# Zigzag_5p_ATtiny_connector.net
KiCad netlist of a schematic drawn in EAGLE
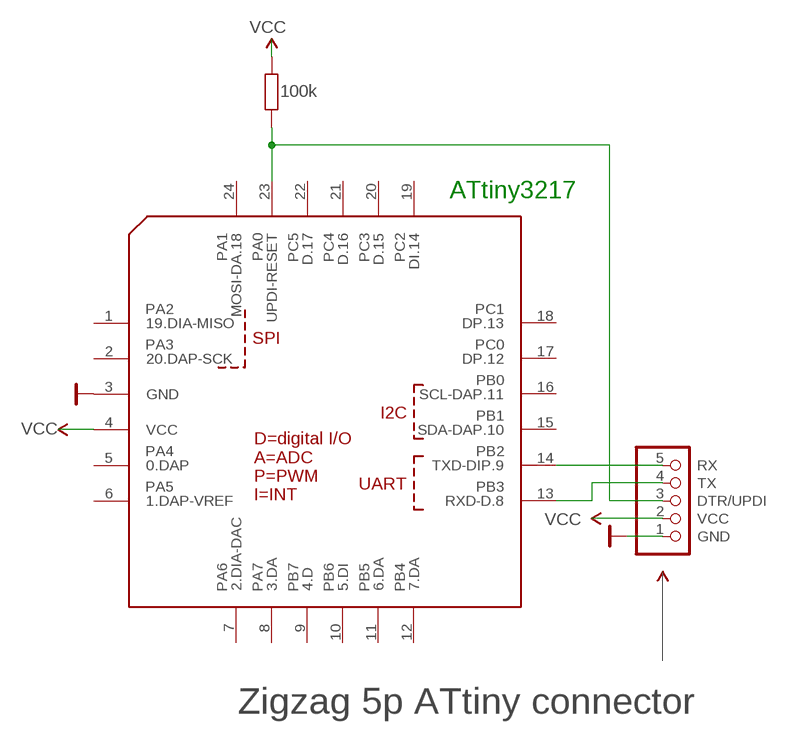
[diagram p0: schematic, sheet 1]

(export (version "E")
  (design (tool "Eeschema 10.0.6"))
  (components
    (comp (ref "J1")
      (value "5 pin 0.05\" ZIGZAG connector")
      (footprint "eagle-import:ZIGZAG-FTDI-UPDI-5P")
      (libsource (lib "eagle-import") (part "ZIGZAG-FTDI-UPDI-5P"))
    )
    (comp (ref "R1")
      (value "100k")
      (footprint "eagle-import:0603")
      (libsource (lib "eagle-import") (part "SMD-R0603"))
    )
    (comp (ref "U2")
      (value "ATtiny3217")
      (footprint "eagle-import:QFN-24")
      (libsource (lib "eagle-import") (part "ATTINY3217-"))
    )
  )
  (nets
    (net (code "1") (name "/VCC") (class "Default")
      (node (ref "J1") (pin "2") (pinfunction "VCC_2") (pintype "passive"))
      (node (ref "R1") (pin "2") (pinfunction "2_2") (pintype "passive"))
      (node (ref "U2") (pin "4") (pinfunction "VCC_4") (pintype "bidirectional"))
    )
    (net (code "2") (name "GND") (class "Default")
      (node (ref "J1") (pin "1") (pinfunction "GND_1") (pintype "passive"))
      (node (ref "U2") (pin "3") (pinfunction "GND_3") (pintype "bidirectional"))
    )
    (net (code "3") (name "Net-(J1-DTR{slash}UPDI)") (class "Default")
      (node (ref "J1") (pin "3") (pinfunction "DTR/UPDI_3") (pintype "passive"))
      (node (ref "R1") (pin "1") (pinfunction "1_1") (pintype "passive"))
      (node (ref "U2") (pin "23") (pinfunction "UPDI-RESET_23") (pintype "bidirectional"))
    )
    (net (code "4") (name "Net-(J1-RX)") (class "Default")
      (node (ref "J1") (pin "5") (pinfunction "RX_5") (pintype "passive"))
      (node (ref "U2") (pin "14") (pinfunction "TXD-DIP.9_14") (pintype "bidirectional"))
    )
    (net (code "5") (name "Net-(J1-TX)") (class "Default")
      (node (ref "J1") (pin "4") (pinfunction "TX_4") (pintype "passive"))
      (node (ref "U2") (pin "13") (pinfunction "RXD-D.8_13") (pintype "bidirectional"))
    )
    (net (code "6") (name "unconnected-(U2-0.DAP-Pad5)") (class "Default")
      (node (ref "U2") (pin "5") (pinfunction "0.DAP_5") (pintype "bidirectional"))
    )
    (net (code "7") (name "unconnected-(U2-1.DAP-VREF-Pad6)") (class "Default")
      (node (ref "U2") (pin "6") (pinfunction "1.DAP-VREF_6") (pintype "bidirectional"))
    )
    (net (code "8") (name "unconnected-(U2-2.DIA-DAC-Pad7)") (class "Default")
      (node (ref "U2") (pin "7") (pinfunction "2.DIA-DAC_7") (pintype "bidirectional"))
    )
    (net (code "9") (name "unconnected-(U2-3.DA-Pad8)") (class "Default")
      (node (ref "U2") (pin "8") (pinfunction "3.DA_8") (pintype "bidirectional"))
    )
    (net (code "10") (name "unconnected-(U2-4.D-Pad9)") (class "Default")
      (node (ref "U2") (pin "9") (pinfunction "4.D_9") (pintype "bidirectional"))
    )
    (net (code "11") (name "unconnected-(U2-5.DI-Pad10)") (class "Default")
      (node (ref "U2") (pin "10") (pinfunction "5.DI_10") (pintype "bidirectional"))
    )
    (net (code "12") (name "unconnected-(U2-6.DA-Pad11)") (class "Default")
      (node (ref "U2") (pin "11") (pinfunction "6.DA_11") (pintype "bidirectional"))
    )
    (net (code "13") (name "unconnected-(U2-7.DA-Pad12)") (class "Default")
      (node (ref "U2") (pin "12") (pinfunction "7.DA_12") (pintype "bidirectional"))
    )
    (net (code "14") (name "unconnected-(U2-19.DIA-MISO-Pad1)") (class "Default")
      (node (ref "U2") (pin "1") (pinfunction "19.DIA-MISO_1") (pintype "bidirectional"))
    )
    (net (code "15") (name "unconnected-(U2-20.DAP-SCK-Pad2)") (class "Default")
      (node (ref "U2") (pin "2") (pinfunction "20.DAP-SCK_2") (pintype "bidirectional"))
    )
    (net (code "16") (name "unconnected-(U2-D.15-Pad20)") (class "Default")
      (node (ref "U2") (pin "20") (pinfunction "D.15_20") (pintype "bidirectional"))
    )
    (net (code "17") (name "unconnected-(U2-D.16-Pad21)") (class "Default")
      (node (ref "U2") (pin "21") (pinfunction "D.16_21") (pintype "bidirectional"))
    )
    (net (code "18") (name "unconnected-(U2-D.17-Pad22)") (class "Default")
      (node (ref "U2") (pin "22") (pinfunction "D.17_22") (pintype "bidirectional"))
    )
    (net (code "19") (name "unconnected-(U2-DI.14-Pad19)") (class "Default")
      (node (ref "U2") (pin "19") (pinfunction "DI.14_19") (pintype "bidirectional"))
    )
    (net (code "20") (name "unconnected-(U2-DP.12-Pad17)") (class "Default")
      (node (ref "U2") (pin "17") (pinfunction "DP.12_17") (pintype "bidirectional"))
    )
    (net (code "21") (name "unconnected-(U2-DP.13-Pad18)") (class "Default")
      (node (ref "U2") (pin "18") (pinfunction "DP.13_18") (pintype "bidirectional"))
    )
    (net (code "22") (name "unconnected-(U2-MOSI-DA.18-Pad24)") (class "Default")
      (node (ref "U2") (pin "24") (pinfunction "MOSI-DA.18_24") (pintype "bidirectional"))
    )
    (net (code "23") (name "unconnected-(U2-SCL-DAP.11-Pad16)") (class "Default")
      (node (ref "U2") (pin "16") (pinfunction "SCL-DAP.11_16") (pintype "bidirectional"))
    )
    (net (code "24") (name "unconnected-(U2-SDA-DAP.10-Pad15)") (class "Default")
      (node (ref "U2") (pin "15") (pinfunction "SDA-DAP.10_15") (pintype "bidirectional"))
    )
  )
)
